# w18-CV-v03_rev5_6.net
KiCad netlist of a schematic drawn in EAGLE
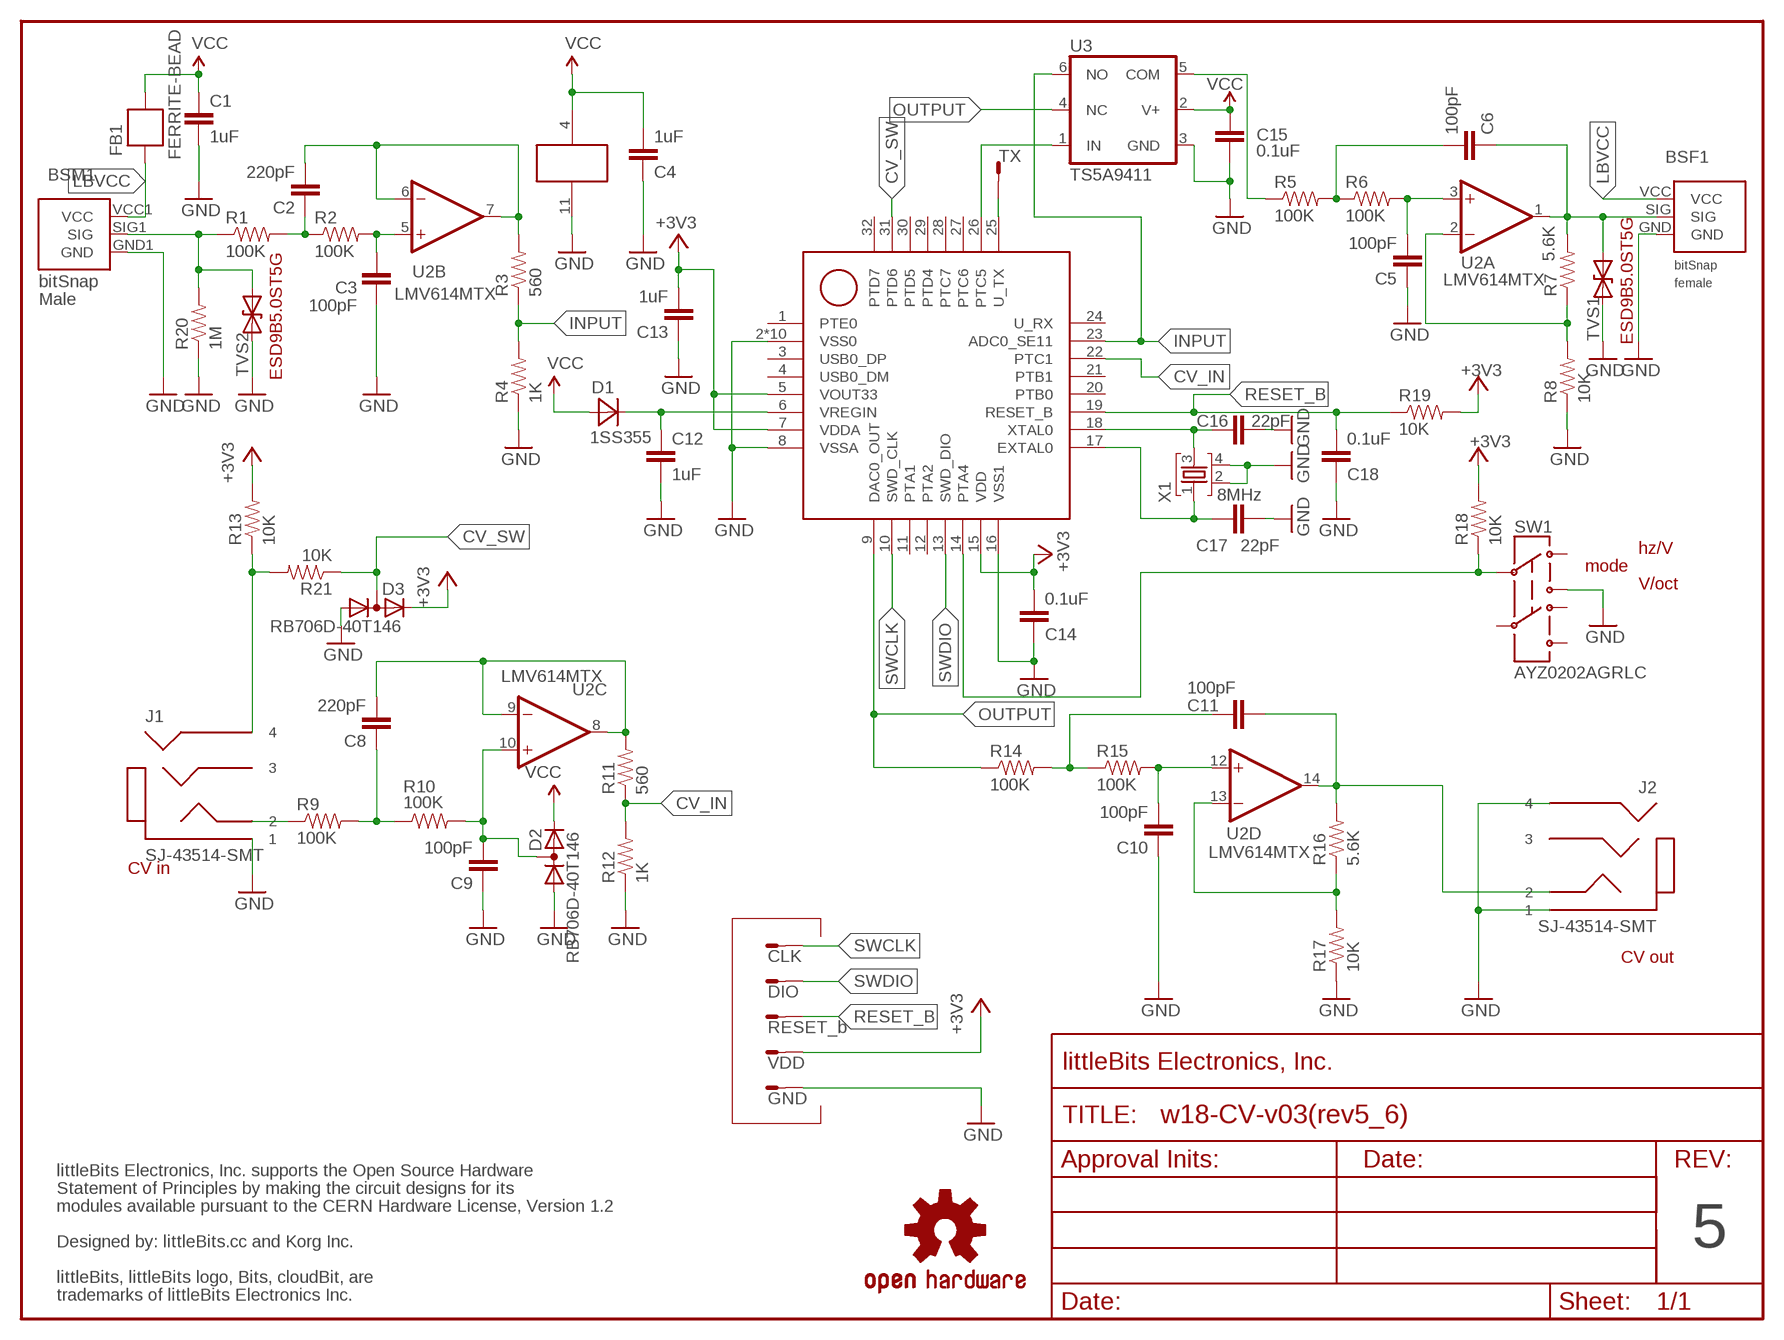
[diagram p0: schematic, sheet 1]

(export (version "E")
  (design (tool "Eeschema 10.0.6"))
  (components
    (comp (ref "BSF1")
      (value "BITSNAP_V03_FEMALE")
      (footprint "eagle-import:BITSNAP_V03_FEMALE")
      (libsource (lib "eagle-import") (part "BITSNAP_V03_FEMALE"))
    )
    (comp (ref "BSM1")
      (value "BITSNAP_V03_MALE")
      (footprint "eagle-import:BITSNAP_V03_MALE")
      (libsource (lib "eagle-import") (part "BITSNAP_V03_MALE"))
    )
    (comp (ref "C1")
      (value "1uF")
      (footprint "eagle-import:CC_1608_0.8_TBR_LB_1PRIMARY")
      (libsource (lib "eagle-import") (part "CC_1608_0.8_TBR_LB_1"))
    )
    (comp (ref "C2")
      (value "220pF")
      (footprint "eagle-import:CC_1608_0.8_TBR_LB_1PRIMARY")
      (libsource (lib "eagle-import") (part "CC_1608_0.8_TBR_LB_1"))
    )
    (comp (ref "C3")
      (value "100pF")
      (footprint "eagle-import:CC_1608_0.8_TBR_LB_1PRIMARY")
      (libsource (lib "eagle-import") (part "CC_1608_0.8_TBR_LB_1"))
    )
    (comp (ref "C4")
      (value "1uF")
      (footprint "eagle-import:CC_1608_0.8_TBR_LB_1PRIMARY")
      (libsource (lib "eagle-import") (part "CC_1608_0.8_TBR_LB_1"))
    )
    (comp (ref "C5")
      (value "100pF")
      (footprint "eagle-import:CC_1608_0.8_TBR_LB_1PRIMARY")
      (libsource (lib "eagle-import") (part "CC_1608_0.8_TBR_LB_1"))
    )
    (comp (ref "C6")
      (value "100pF")
      (footprint "eagle-import:CC_1608_0.8_TBR_LB_1PRIMARY")
      (libsource (lib "eagle-import") (part "CC_1608_0.8_TBR_LB_1"))
    )
    (comp (ref "C8")
      (value "220pF")
      (footprint "eagle-import:CC_1608_0.8_TBR_LB_1PRIMARY")
      (libsource (lib "eagle-import") (part "CC_1608_0.8_TBR_LB_1"))
    )
    (comp (ref "C9")
      (value "100pF")
      (footprint "eagle-import:CC_1608_0.8_TBR_LB_1PRIMARY")
      (libsource (lib "eagle-import") (part "CC_1608_0.8_TBR_LB_1"))
    )
    (comp (ref "C10")
      (value "100pF")
      (footprint "eagle-import:CC_1608_0.8_TBR_LB_1PRIMARY")
      (libsource (lib "eagle-import") (part "CC_1608_0.8_TBR_LB_1"))
    )
    (comp (ref "C11")
      (value "100pF")
      (footprint "eagle-import:CC_1608_0.8_TBR_LB_1PRIMARY")
      (libsource (lib "eagle-import") (part "CC_1608_0.8_TBR_LB_1"))
    )
    (comp (ref "C12")
      (value "1uF")
      (footprint "eagle-import:CC_1608_0.8_TBR_LB_1PRIMARY")
      (libsource (lib "eagle-import") (part "CC_1608_0.8_TBR_LB_1"))
    )
    (comp (ref "C13")
      (value "1uF")
      (footprint "eagle-import:CC_1608_0.8_TBR_LB_1PRIMARY")
      (libsource (lib "eagle-import") (part "CC_1608_0.8_TBR_LB_1"))
    )
    (comp (ref "C14")
      (value "0.1uF")
      (footprint "eagle-import:CC_1608_0.8_TBR_LB_1PRIMARY")
      (libsource (lib "eagle-import") (part "CC_1608_0.8_TBR_LB_1"))
    )
    (comp (ref "C15")
      (value "0.1uF")
      (footprint "eagle-import:CC_1608_0.8_TBR_LB_1PRIMARY")
      (libsource (lib "eagle-import") (part "CC_1608_0.8_TBR_LB_1"))
    )
    (comp (ref "C16")
      (value "22pF")
      (footprint "eagle-import:CC_1608_0.8_TBR_LB_1PRIMARY")
      (libsource (lib "eagle-import") (part "CC_1608_0.8_TBR_LB_1"))
    )
    (comp (ref "C17")
      (value "22pF")
      (footprint "eagle-import:CC_1608_0.8_TBR_LB_1PRIMARY")
      (libsource (lib "eagle-import") (part "CC_1608_0.8_TBR_LB_1"))
    )
    (comp (ref "C18")
      (value "0.1uF")
      (footprint "eagle-import:CC_1608_0.8_TBR_LB_1PRIMARY")
      (libsource (lib "eagle-import") (part "CC_1608_0.8_TBR_LB_1"))
    )
    (comp (ref "D1")
      (value "1SS355")
      (footprint "eagle-import:DISC_ROHM-UMD2_#_TBR_LB_1PRIMARY")
      (libsource (lib "eagle-import") (part "DISC_ROHM-UMD2_#_TBR_LB_1"))
    )
    (comp (ref "D2")
      (value "RB706D-40T146")
      (footprint "eagle-import:SOT23C")
      (libsource (lib "eagle-import") (part "DIODE_SERIES_A1-K2-AK3_"))
    )
    (comp (ref "D3")
      (value "RB706D-40T146")
      (footprint "eagle-import:SOT23C")
      (libsource (lib "eagle-import") (part "DIODE_SERIES_A1-K2-AK3_"))
    )
    (comp (ref "FB1")
      (value "FERRITE-BEAD")
      (footprint "eagle-import:R0603")
      (libsource (lib "eagle-import") (part "FERRITE-BEAD"))
    )
    (comp (ref "FRAME1")
      (value "FRAME-LETTER-OHWOHW")
      (footprint "eagle-import:FABDWG01-OHW")
      (libsource (lib "eagle-import") (part "FRAME-LETTER-OHWOHW"))
    )
    (comp (ref "J1")
      (value "SJ-43514-SMT")
      (footprint "eagle-import:LB_K_CN_SJ-43514-SMT_LB")
      (libsource (lib "eagle-import") (part "LB_K_CN_SJ-43514-SMT_LB"))
    )
    (comp (ref "J2")
      (value "SJ-43514-SMT")
      (footprint "eagle-import:LB_K_CN_SJ-43514-SMT_LB")
      (libsource (lib "eagle-import") (part "LB_K_CN_SJ-43514-SMT_LB"))
    )
    (comp (ref "JP1")
      (value "GND")
      (footprint "eagle-import:TEST_POINT_1PRIMARY")
      (libsource (lib "eagle-import") (part "TEST_POINT_1"))
    )
    (comp (ref "JP2")
      (value "VDD")
      (footprint "eagle-import:TEST_POINT_1PRIMARY")
      (libsource (lib "eagle-import") (part "TEST_POINT_1"))
    )
    (comp (ref "JP3")
      (value "RESET_b")
      (footprint "eagle-import:TEST_POINT_1PRIMARY")
      (libsource (lib "eagle-import") (part "TEST_POINT_1"))
    )
    (comp (ref "JP4")
      (value "DIO")
      (footprint "eagle-import:TEST_POINT_1PRIMARY")
      (libsource (lib "eagle-import") (part "TEST_POINT_1"))
    )
    (comp (ref "JP5")
      (value "CLK")
      (footprint "eagle-import:TEST_POINT_1PRIMARY")
      (libsource (lib "eagle-import") (part "TEST_POINT_1"))
    )
    (comp (ref "JP6")
      (value "TX")
      (footprint "eagle-import:TEST_POINT_1PRIMARY")
      (libsource (lib "eagle-import") (part "TEST_POINT_1"))
    )
    (comp (ref "R1")
      (value "100K")
      (footprint "eagle-import:R_1608_LB")
      (libsource (lib "eagle-import") (part "R_1608_LB"))
    )
    (comp (ref "R2")
      (value "100K")
      (footprint "eagle-import:R_1608_LB")
      (libsource (lib "eagle-import") (part "R_1608_LB"))
    )
    (comp (ref "R3")
      (value "560")
      (footprint "eagle-import:R_1608_LB")
      (libsource (lib "eagle-import") (part "R_1608_LB"))
    )
    (comp (ref "R4")
      (value "1K")
      (footprint "eagle-import:R_1608_LB")
      (libsource (lib "eagle-import") (part "R_1608_LB"))
    )
    (comp (ref "R5")
      (value "100K")
      (footprint "eagle-import:R_1608_LB")
      (libsource (lib "eagle-import") (part "R_1608_LB"))
    )
    (comp (ref "R6")
      (value "100K")
      (footprint "eagle-import:R_1608_LB")
      (libsource (lib "eagle-import") (part "R_1608_LB"))
    )
    (comp (ref "R7")
      (value "5.6K")
      (footprint "eagle-import:R_1608_LB")
      (libsource (lib "eagle-import") (part "R_1608_LB"))
    )
    (comp (ref "R8")
      (value "10K")
      (footprint "eagle-import:R_1608_LB")
      (libsource (lib "eagle-import") (part "R_1608_LB"))
    )
    (comp (ref "R9")
      (value "100K")
      (footprint "eagle-import:R_1608_LB")
      (libsource (lib "eagle-import") (part "R_1608_LB"))
    )
    (comp (ref "R10")
      (value "100K")
      (footprint "eagle-import:R_1608_LB")
      (libsource (lib "eagle-import") (part "R_1608_LB"))
    )
    (comp (ref "R11")
      (value "560")
      (footprint "eagle-import:R_1608_LB")
      (libsource (lib "eagle-import") (part "R_1608_LB"))
    )
    (comp (ref "R12")
      (value "1K")
      (footprint "eagle-import:R_1608_LB")
      (libsource (lib "eagle-import") (part "R_1608_LB"))
    )
    (comp (ref "R13")
      (value "10K")
      (footprint "eagle-import:R_1608_LB")
      (libsource (lib "eagle-import") (part "R_1608_LB"))
    )
    (comp (ref "R14")
      (value "100K")
      (footprint "eagle-import:R_1608_LB")
      (libsource (lib "eagle-import") (part "R_1608_LB"))
    )
    (comp (ref "R15")
      (value "100K")
      (footprint "eagle-import:R_1608_LB")
      (libsource (lib "eagle-import") (part "R_1608_LB"))
    )
    (comp (ref "R16")
      (value "5.6K")
      (footprint "eagle-import:R_1608_LB")
      (libsource (lib "eagle-import") (part "R_1608_LB"))
    )
    (comp (ref "R17")
      (value "10K")
      (footprint "eagle-import:R_1608_LB")
      (libsource (lib "eagle-import") (part "R_1608_LB"))
    )
    (comp (ref "R18")
      (value "10K")
      (footprint "eagle-import:R_1608_LB")
      (libsource (lib "eagle-import") (part "R_1608_LB"))
    )
    (comp (ref "R19")
      (value "10K")
      (footprint "eagle-import:R_1608_LB")
      (libsource (lib "eagle-import") (part "R_1608_LB"))
    )
    (comp (ref "R20")
      (value "1M")
      (footprint "eagle-import:R_1608_LB")
      (libsource (lib "eagle-import") (part "R_1608_LB"))
    )
    (comp (ref "R21")
      (value "10K")
      (footprint "eagle-import:R_1608_LB")
      (libsource (lib "eagle-import") (part "R_1608_LB"))
    )
    (comp (ref "SW1")
      (value "AYZ0202AGRLC")
      (footprint "eagle-import:SW_MS-22C01_#_TBR_LB_1PRIMARY")
      (libsource (lib "eagle-import") (part "SW_MS-22C01_#_TBR_LB_1"))
    )
    (comp (ref "TVS1")
      (value "ESD9B5.0ST5G")
      (footprint "eagle-import:SOD-923")
      (fields (field (name "MPN") "ESD9B5.0ST5G"))
      (libsource (lib "eagle-import") (part "DIODE-TVSSOD-923"))
    )
    (comp (ref "TVS2")
      (value "ESD9B5.0ST5G")
      (footprint "eagle-import:SOD-923")
      (fields (field (name "MPN") "ESD9B5.0ST5G"))
      (libsource (lib "eagle-import") (part "DIODE-TVSSOD-923"))
    )
    (comp (ref "U$1")
      (value "OSHWCREDIT-KORG")
      (footprint "eagle-import:OSHWCREDIT-KORG")
      (libsource (lib "eagle-import") (part "OSHWCREDIT-KORG"))
    )
    (comp (ref "U$5")
      (value "OSHW-LOGOL")
      (footprint "eagle-import:OSHW-LOGO-L")
      (libsource (lib "eagle-import") (part "OSHW-LOGOL"))
    )
    (comp (ref "U1")
      (value "MKL26Z64VFM4")
      (footprint "eagle-import:IC_TI-QFN32_0.5_TBR_LB_1PRIMARY")
      (libsource (lib "eagle-import") (part "IC_TI-QFN32_0.5_TBR_LB_1"))
    )
    (comp (ref "U2")
      (value "LMV614MTX")
      (footprint "eagle-import:IC_TSSOP14-225_0.65_TBR_LB_1PRIMARY")
      (libsource (lib "eagle-import") (part "IC_TSSOP14-225_0.65_TBR_LB_1"))
    )
    (comp (ref "U3")
      (value "TS5A9411")
      (footprint "eagle-import:IC_SSOP6-W2.1_0.65_TBR_LB_1PRIMARY")
      (libsource (lib "eagle-import") (part "IC_SSOP6-W2.1_0.65_TBR_LB_1"))
    )
    (comp (ref "X1")
      (value "8MHz")
      (footprint "eagle-import:X_ROSON_RT5_#_TBR_LB_1PRIMARY")
      (libsource (lib "eagle-import") (part "X_ROSON_RT5_#_TBR_LB_1"))
    )
  )
  (nets
    (net (code "1") (name "+3V3") (class "Default")
      (node (ref "C13") (pin "2") (pinfunction "2_2") (pintype "passive"))
      (node (ref "C14") (pin "2") (pinfunction "2_2") (pintype "passive"))
      (node (ref "D3") (pin "2") (pinfunction "K_2") (pintype "passive"))
      (node (ref "JP2") (pin "1") (pinfunction "S_1") (pintype "passive"))
      (node (ref "R13") (pin "2") (pinfunction "2_2") (pintype "passive"))
      (node (ref "R18") (pin "2") (pinfunction "2_2") (pintype "passive"))
      (node (ref "R19") (pin "2") (pinfunction "2_2") (pintype "passive"))
      (node (ref "U1") (pin "15") (pinfunction "VDD_15") (pintype "bidirectional"))
      (node (ref "U1") (pin "5") (pinfunction "VOUT33_5") (pintype "bidirectional"))
      (node (ref "U1") (pin "7") (pinfunction "VDDA_7") (pintype "bidirectional"))
    )
    (net (code "2") (name "CV_IN") (class "Default")
      (node (ref "R11") (pin "1") (pinfunction "1_1") (pintype "passive"))
      (node (ref "R12") (pin "2") (pinfunction "2_2") (pintype "passive"))
      (node (ref "U1") (pin "22") (pinfunction "PTC1_22") (pintype "bidirectional"))
    )
    (net (code "3") (name "CV_SW") (class "Default")
      (node (ref "D3") (pin "3") (pinfunction "AK_3") (pintype "passive"))
      (node (ref "R21") (pin "1") (pinfunction "1_1") (pintype "passive"))
      (node (ref "U1") (pin "31") (pinfunction "PTD6_31") (pintype "bidirectional"))
    )
    (net (code "4") (name "GND") (class "Default")
      (node (ref "BSF1") (pin "GND") (pinfunction "GND_GND") (pintype "bidirectional"))
      (node (ref "BSM1") (pin "GND1") (pinfunction "GND_GND1") (pintype "bidirectional"))
      (node (ref "C1") (pin "2") (pinfunction "2_2") (pintype "passive"))
      (node (ref "C10") (pin "1") (pinfunction "1_1") (pintype "passive"))
      (node (ref "C12") (pin "2") (pinfunction "2_2") (pintype "passive"))
      (node (ref "C13") (pin "1") (pinfunction "1_1") (pintype "passive"))
      (node (ref "C14") (pin "1") (pinfunction "1_1") (pintype "passive"))
      (node (ref "C15") (pin "1") (pinfunction "1_1") (pintype "passive"))
      (node (ref "C16") (pin "1") (pinfunction "1_1") (pintype "passive"))
      (node (ref "C17") (pin "1") (pinfunction "1_1") (pintype "passive"))
      (node (ref "C18") (pin "1") (pinfunction "1_1") (pintype "passive"))
      (node (ref "C3") (pin "1") (pinfunction "1_1") (pintype "passive"))
      (node (ref "C4") (pin "1") (pinfunction "1_1") (pintype "passive"))
      (node (ref "C5") (pin "1") (pinfunction "1_1") (pintype "passive"))
      (node (ref "C9") (pin "1") (pinfunction "1_1") (pintype "passive"))
      (node (ref "D2") (pin "1") (pinfunction "A_1") (pintype "passive"))
      (node (ref "D3") (pin "1") (pinfunction "A_1") (pintype "passive"))
      (node (ref "J1") (pin "1") (pinfunction "1_1") (pintype "bidirectional"))
      (node (ref "J2") (pin "1") (pinfunction "1_1") (pintype "bidirectional"))
      (node (ref "J2") (pin "4") (pinfunction "4_4") (pintype "bidirectional"))
      (node (ref "JP1") (pin "1") (pinfunction "S_1") (pintype "passive"))
      (node (ref "R12") (pin "1") (pinfunction "1_1") (pintype "passive"))
      (node (ref "R17") (pin "1") (pinfunction "1_1") (pintype "passive"))
      (node (ref "R20") (pin "1") (pinfunction "1_1") (pintype "passive"))
      (node (ref "R4") (pin "1") (pinfunction "1_1") (pintype "passive"))
      (node (ref "R8") (pin "1") (pinfunction "1_1") (pintype "passive"))
      (node (ref "SW1") (pin "3") (pinfunction "3_3") (pintype "bidirectional"))
      (node (ref "TVS1") (pin "1") (pinfunction "A_1") (pintype "passive"))
      (node (ref "TVS2") (pin "1") (pinfunction "A_1") (pintype "passive"))
      (node (ref "U1") (pin "16") (pinfunction "VSS1_16") (pintype "bidirectional"))
      (node (ref "U1") (pin "2") (pinfunction "VSS0_2") (pintype "bidirectional"))
      (node (ref "U1") (pin "33") (pinfunction "VSS0_33") (pintype "bidirectional"))
      (node (ref "U1") (pin "34") (pinfunction "VSS0_34") (pintype "bidirectional"))
      (node (ref "U1") (pin "35") (pinfunction "VSS0_35") (pintype "bidirectional"))
      (node (ref "U1") (pin "36") (pinfunction "VSS0_36") (pintype "bidirectional"))
      (node (ref "U1") (pin "37") (pinfunction "VSS0_37") (pintype "bidirectional"))
      (node (ref "U1") (pin "38") (pinfunction "VSS0_38") (pintype "bidirectional"))
      (node (ref "U1") (pin "39") (pinfunction "VSS0_39") (pintype "bidirectional"))
      (node (ref "U1") (pin "40") (pinfunction "VSS0_40") (pintype "bidirectional"))
      (node (ref "U1") (pin "41") (pinfunction "VSS0_41") (pintype "bidirectional"))
      (node (ref "U1") (pin "8") (pinfunction "VSSA_8") (pintype "bidirectional"))
      (node (ref "U2") (pin "11") (pinfunction "V-_11") (pintype "power_in"))
      (node (ref "U3") (pin "3") (pinfunction "GND_3") (pintype "power_in"))
      (node (ref "X1") (pin "2") (pinfunction "2_2") (pintype "passive"))
      (node (ref "X1") (pin "4") (pinfunction "4_4") (pintype "passive"))
    )
    (net (code "5") (name "INPUT") (class "Default")
      (node (ref "R3") (pin "1") (pinfunction "1_1") (pintype "passive"))
      (node (ref "R4") (pin "2") (pinfunction "2_2") (pintype "passive"))
      (node (ref "U1") (pin "23") (pinfunction "ADC0_SE11_23") (pintype "bidirectional"))
      (node (ref "U3") (pin "6") (pinfunction "NO_6") (pintype "bidirectional"))
    )
    (net (code "6") (name "LBVCC") (class "Default")
      (node (ref "BSF1") (pin "VCC") (pinfunction "VCC_VCC") (pintype "bidirectional"))
      (node (ref "BSM1") (pin "VCC1") (pinfunction "VCC_VCC1") (pintype "bidirectional"))
      (node (ref "FB1") (pin "2") (pinfunction "P$2_2") (pintype "bidirectional"))
    )
    (net (code "7") (name "Net-(BSM1-SIG)") (class "Default")
      (node (ref "BSM1") (pin "SIG1") (pinfunction "SIG_SIG1") (pintype "bidirectional"))
      (node (ref "R1") (pin "1") (pinfunction "1_1") (pintype "passive"))
      (node (ref "R20") (pin "2") (pinfunction "2_2") (pintype "passive"))
      (node (ref "TVS2") (pin "2") (pinfunction "C_2") (pintype "passive"))
    )
    (net (code "8") (name "Net-(C2-Pad1)") (class "Default")
      (node (ref "C2") (pin "1") (pinfunction "1_1") (pintype "passive"))
      (node (ref "R1") (pin "2") (pinfunction "2_2") (pintype "passive"))
      (node (ref "R2") (pin "1") (pinfunction "1_1") (pintype "passive"))
    )
    (net (code "9") (name "Net-(C6-Pad2)") (class "Default")
      (node (ref "C6") (pin "2") (pinfunction "2_2") (pintype "passive"))
      (node (ref "R5") (pin "2") (pinfunction "2_2") (pintype "passive"))
      (node (ref "R6") (pin "1") (pinfunction "1_1") (pintype "passive"))
    )
    (net (code "10") (name "Net-(C8-Pad1)") (class "Default")
      (node (ref "C8") (pin "1") (pinfunction "1_1") (pintype "passive"))
      (node (ref "R10") (pin "1") (pinfunction "1_1") (pintype "passive"))
      (node (ref "R9") (pin "2") (pinfunction "2_2") (pintype "passive"))
    )
    (net (code "11") (name "Net-(C11-Pad2)") (class "Default")
      (node (ref "C11") (pin "2") (pinfunction "2_2") (pintype "passive"))
      (node (ref "R14") (pin "2") (pinfunction "2_2") (pintype "passive"))
      (node (ref "R15") (pin "1") (pinfunction "1_1") (pintype "passive"))
    )
    (net (code "12") (name "Net-(D2-AK)") (class "Default")
      (node (ref "C9") (pin "2") (pinfunction "2_2") (pintype "passive"))
      (node (ref "D2") (pin "3") (pinfunction "AK_3") (pintype "passive"))
      (node (ref "R10") (pin "2") (pinfunction "2_2") (pintype "passive"))
      (node (ref "U2") (pin "10") (pinfunction "+IN_10") (pintype "input"))
    )
    (net (code "13") (name "Net-(J1-Pad2)") (class "Default")
      (node (ref "J1") (pin "2") (pinfunction "2_2") (pintype "bidirectional"))
      (node (ref "R9") (pin "1") (pinfunction "1_1") (pintype "passive"))
    )
    (net (code "14") (name "Net-(J1-Pad4)") (class "Default")
      (node (ref "J1") (pin "4") (pinfunction "4_4") (pintype "bidirectional"))
      (node (ref "R13") (pin "1") (pinfunction "1_1") (pintype "passive"))
      (node (ref "R21") (pin "2") (pinfunction "2_2") (pintype "passive"))
    )
    (net (code "15") (name "Net-(JP6-S)") (class "Default")
      (node (ref "JP6") (pin "1") (pinfunction "S_1") (pintype "passive"))
      (node (ref "U1") (pin "25") (pinfunction "U_TX_25") (pintype "bidirectional"))
    )
    (net (code "16") (name "Net-(TVS1-C)") (class "Default")
      (node (ref "BSF1") (pin "SIG") (pinfunction "SIG_SIG") (pintype "bidirectional"))
      (node (ref "C6") (pin "1") (pinfunction "1_1") (pintype "passive"))
      (node (ref "R7") (pin "2") (pinfunction "2_2") (pintype "passive"))
      (node (ref "TVS1") (pin "2") (pinfunction "C_2") (pintype "passive"))
      (node (ref "U2") (pin "1") (pinfunction "OUT_1") (pintype "output"))
    )
    (net (code "17") (name "Net-(U1-EXTAL0)") (class "Default")
      (node (ref "C17") (pin "2") (pinfunction "2_2") (pintype "passive"))
      (node (ref "U1") (pin "17") (pinfunction "EXTAL0_17") (pintype "bidirectional"))
      (node (ref "X1") (pin "1") (pinfunction "1_1") (pintype "passive"))
    )
    (net (code "18") (name "Net-(U1-PTA4)") (class "Default")
      (node (ref "R18") (pin "1") (pinfunction "1_1") (pintype "passive"))
      (node (ref "SW1") (pin "2") (pinfunction "2_2") (pintype "bidirectional"))
      (node (ref "U1") (pin "14") (pinfunction "PTA4_14") (pintype "bidirectional"))
    )
    (net (code "19") (name "Net-(U1-PTC5)") (class "Default")
      (node (ref "U1") (pin "26") (pinfunction "PTC5_26") (pintype "bidirectional"))
      (node (ref "U3") (pin "1") (pinfunction "IN_1") (pintype "input"))
    )
    (net (code "20") (name "Net-(U1-VREGIN)") (class "Default")
      (node (ref "C12") (pin "1") (pinfunction "1_1") (pintype "passive"))
      (node (ref "D1") (pin "2") (pinfunction "2_2") (pintype "passive"))
      (node (ref "U1") (pin "6") (pinfunction "VREGIN_6") (pintype "bidirectional"))
    )
    (net (code "21") (name "Net-(U1-XTAL0)") (class "Default")
      (node (ref "C16") (pin "2") (pinfunction "2_2") (pintype "passive"))
      (node (ref "U1") (pin "18") (pinfunction "XTAL0_18") (pintype "bidirectional"))
      (node (ref "X1") (pin "3") (pinfunction "3_3") (pintype "passive"))
    )
    (net (code "22") (name "Net-(U2A-+IN)") (class "Default")
      (node (ref "C5") (pin "2") (pinfunction "2_2") (pintype "passive"))
      (node (ref "R6") (pin "2") (pinfunction "2_2") (pintype "passive"))
      (node (ref "U2") (pin "3") (pinfunction "+IN_3") (pintype "input"))
    )
    (net (code "23") (name "Net-(U2A--IN)") (class "Default")
      (node (ref "R7") (pin "1") (pinfunction "1_1") (pintype "passive"))
      (node (ref "R8") (pin "2") (pinfunction "2_2") (pintype "passive"))
      (node (ref "U2") (pin "2") (pinfunction "-IN_2") (pintype "input"))
    )
    (net (code "24") (name "Net-(U2B-+IN)") (class "Default")
      (node (ref "C3") (pin "2") (pinfunction "2_2") (pintype "passive"))
      (node (ref "R2") (pin "2") (pinfunction "2_2") (pintype "passive"))
      (node (ref "U2") (pin "5") (pinfunction "+IN_5") (pintype "input"))
    )
    (net (code "25") (name "Net-(U2B--IN)") (class "Default")
      (node (ref "C2") (pin "2") (pinfunction "2_2") (pintype "passive"))
      (node (ref "R3") (pin "2") (pinfunction "2_2") (pintype "passive"))
      (node (ref "U2") (pin "6") (pinfunction "-IN_6") (pintype "input"))
      (node (ref "U2") (pin "7") (pinfunction "OUT_7") (pintype "output"))
    )
    (net (code "26") (name "Net-(U2C--IN)") (class "Default")
      (node (ref "C8") (pin "2") (pinfunction "2_2") (pintype "passive"))
      (node (ref "R11") (pin "2") (pinfunction "2_2") (pintype "passive"))
      (node (ref "U2") (pin "8") (pinfunction "OUT_8") (pintype "output"))
      (node (ref "U2") (pin "9") (pinfunction "-IN_9") (pintype "input"))
    )
    (net (code "27") (name "Net-(U2D-+IN)") (class "Default")
      (node (ref "C10") (pin "2") (pinfunction "2_2") (pintype "passive"))
      (node (ref "R15") (pin "2") (pinfunction "2_2") (pintype "passive"))
      (node (ref "U2") (pin "12") (pinfunction "+IN_12") (pintype "input"))
    )
    (net (code "28") (name "Net-(U2D--IN)") (class "Default")
      (node (ref "R16") (pin "1") (pinfunction "1_1") (pintype "passive"))
      (node (ref "R17") (pin "2") (pinfunction "2_2") (pintype "passive"))
      (node (ref "U2") (pin "13") (pinfunction "-IN_13") (pintype "input"))
    )
    (net (code "29") (name "Net-(U2D-OUT)") (class "Default")
      (node (ref "C11") (pin "1") (pinfunction "1_1") (pintype "passive"))
      (node (ref "J2") (pin "2") (pinfunction "2_2") (pintype "bidirectional"))
      (node (ref "R16") (pin "2") (pinfunction "2_2") (pintype "passive"))
      (node (ref "U2") (pin "14") (pinfunction "OUT_14") (pintype "output"))
    )
    (net (code "30") (name "Net-(U3-COM)") (class "Default")
      (node (ref "R5") (pin "1") (pinfunction "1_1") (pintype "passive"))
      (node (ref "U3") (pin "5") (pinfunction "COM_5") (pintype "bidirectional"))
    )
    (net (code "31") (name "OUTPUT") (class "Default")
      (node (ref "R14") (pin "1") (pinfunction "1_1") (pintype "passive"))
      (node (ref "U1") (pin "9") (pinfunction "DAC0_OUT_9") (pintype "bidirectional"))
      (node (ref "U3") (pin "4") (pinfunction "NC_4") (pintype "bidirectional"))
    )
    (net (code "32") (name "RESET_B") (class "Default")
      (node (ref "C18") (pin "2") (pinfunction "2_2") (pintype "passive"))
      (node (ref "JP3") (pin "1") (pinfunction "S_1") (pintype "passive"))
      (node (ref "R19") (pin "1") (pinfunction "1_1") (pintype "passive"))
      (node (ref "U1") (pin "19") (pinfunction "RESET_B_19") (pintype "bidirectional"))
    )
    (net (code "33") (name "SWCLK") (class "Default")
      (node (ref "JP5") (pin "1") (pinfunction "S_1") (pintype "passive"))
      (node (ref "U1") (pin "10") (pinfunction "SWD_CLK_10") (pintype "bidirectional"))
    )
    (net (code "34") (name "SWDIO") (class "Default")
      (node (ref "JP4") (pin "1") (pinfunction "S_1") (pintype "passive"))
      (node (ref "U1") (pin "13") (pinfunction "SWD_DIO_13") (pintype "bidirectional"))
    )
    (net (code "35") (name "VCC") (class "Default")
      (node (ref "C1") (pin "1") (pinfunction "1_1") (pintype "passive"))
      (node (ref "C15") (pin "2") (pinfunction "2_2") (pintype "passive"))
      (node (ref "C4") (pin "2") (pinfunction "2_2") (pintype "passive"))
      (node (ref "D1") (pin "1") (pinfunction "1_1") (pintype "passive"))
      (node (ref "D2") (pin "2") (pinfunction "K_2") (pintype "passive"))
      (node (ref "FB1") (pin "1") (pinfunction "P$1_1") (pintype "bidirectional"))
      (node (ref "U2") (pin "4") (pinfunction "V+_4") (pintype "power_in"))
      (node (ref "U3") (pin "2") (pinfunction "V+_2") (pintype "power_in"))
    )
    (net (code "36") (name "unconnected-(J1-Pad3)") (class "Default")
      (node (ref "J1") (pin "3") (pinfunction "3_3") (pintype "bidirectional"))
    )
    (net (code "37") (name "unconnected-(J2-Pad3)") (class "Default")
      (node (ref "J2") (pin "3") (pinfunction "3_3") (pintype "bidirectional"))
    )
    (net (code "38") (name "unconnected-(SW1-Pad1)") (class "Default")
      (node (ref "SW1") (pin "1") (pinfunction "1_1") (pintype "bidirectional"))
    )
    (net (code "39") (name "unconnected-(SW1-Pad4)") (class "Default")
      (node (ref "SW1") (pin "4") (pinfunction "4_4") (pintype "bidirectional"))
    )
    (net (code "40") (name "unconnected-(SW1-Pad5)") (class "Default")
      (node (ref "SW1") (pin "5") (pinfunction "5_5") (pintype "bidirectional"))
    )
    (net (code "41") (name "unconnected-(SW1-Pad6)") (class "Default")
      (node (ref "SW1") (pin "6") (pinfunction "6_6") (pintype "bidirectional"))
    )
    (net (code "42") (name "unconnected-(U1-PTA1-Pad11)") (class "Default")
      (node (ref "U1") (pin "11") (pinfunction "PTA1_11") (pintype "bidirectional"))
    )
    (net (code "43") (name "unconnected-(U1-PTA2-Pad12)") (class "Default")
      (node (ref "U1") (pin "12") (pinfunction "PTA2_12") (pintype "bidirectional"))
    )
    (net (code "44") (name "unconnected-(U1-PTB0-Pad20)") (class "Default")
      (node (ref "U1") (pin "20") (pinfunction "PTB0_20") (pintype "bidirectional"))
    )
    (net (code "45") (name "unconnected-(U1-PTB1-Pad21)") (class "Default")
      (node (ref "U1") (pin "21") (pinfunction "PTB1_21") (pintype "bidirectional"))
    )
    (net (code "46") (name "unconnected-(U1-PTC6-Pad27)") (class "Default")
      (node (ref "U1") (pin "27") (pinfunction "PTC6_27") (pintype "bidirectional"))
    )
    (net (code "47") (name "unconnected-(U1-PTC7-Pad28)") (class "Default")
      (node (ref "U1") (pin "28") (pinfunction "PTC7_28") (pintype "bidirectional"))
    )
    (net (code "48") (name "unconnected-(U1-PTD4-Pad29)") (class "Default")
      (node (ref "U1") (pin "29") (pinfunction "PTD4_29") (pintype "bidirectional"))
    )
    (net (code "49") (name "unconnected-(U1-PTD5-Pad30)") (class "Default")
      (node (ref "U1") (pin "30") (pinfunction "PTD5_30") (pintype "bidirectional"))
    )
    (net (code "50") (name "unconnected-(U1-PTD7-Pad32)") (class "Default")
      (node (ref "U1") (pin "32") (pinfunction "PTD7_32") (pintype "bidirectional"))
    )
    (net (code "51") (name "unconnected-(U1-PTE0-Pad1)") (class "Default")
      (node (ref "U1") (pin "1") (pinfunction "PTE0_1") (pintype "bidirectional"))
    )
    (net (code "52") (name "unconnected-(U1-USB0_DM-Pad4)") (class "Default")
      (node (ref "U1") (pin "4") (pinfunction "USB0_DM_4") (pintype "bidirectional"))
    )
    (net (code "53") (name "unconnected-(U1-USB0_DP-Pad3)") (class "Default")
      (node (ref "U1") (pin "3") (pinfunction "USB0_DP_3") (pintype "bidirectional"))
    )
    (net (code "54") (name "unconnected-(U1-U_RX-Pad24)") (class "Default")
      (node (ref "U1") (pin "24") (pinfunction "U_RX_24") (pintype "bidirectional"))
    )
  )
)
